# Buck_V2_1.net
KiCad netlist of a schematic drawn in EAGLE
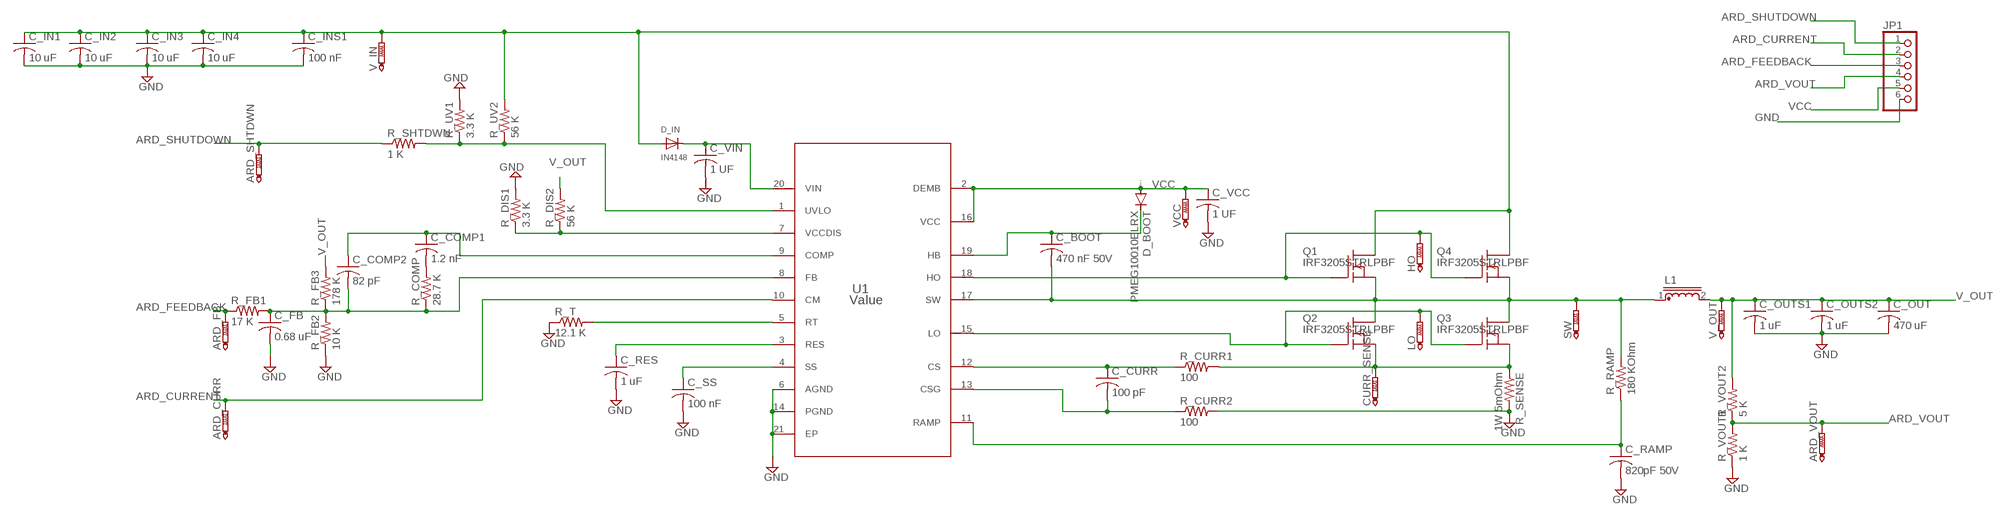
[diagram p0: schematic, sheet 1]

(export (version "E")
  (design (tool "Eeschema 10.0.6"))
  (components
    (comp (ref "ARD_CURR")
      (value "PTR1TP20R")
      (footprint "eagle-import:TP20R")
      (libsource (lib "eagle-import") (part "PTR1TP20R"))
    )
    (comp (ref "ARD_FB")
      (value "PTR1TP20R")
      (footprint "eagle-import:TP20R")
      (libsource (lib "eagle-import") (part "PTR1TP20R"))
    )
    (comp (ref "ARD_SHTDWN")
      (value "PTR1TP20R")
      (footprint "eagle-import:TP20R")
      (libsource (lib "eagle-import") (part "PTR1TP20R"))
    )
    (comp (ref "ARD_VOUT")
      (value "PTR1TP20R")
      (footprint "eagle-import:TP20R")
      (libsource (lib "eagle-import") (part "PTR1TP20R"))
    )
    (comp (ref "CURR_SENSE")
      (value "PTR1TP20R")
      (footprint "eagle-import:TP20R")
      (libsource (lib "eagle-import") (part "PTR1TP20R"))
    )
    (comp (ref "C_BOOT")
      (value "470 nF 50V")
      (footprint "eagle-import:C0603")
      (libsource (lib "eagle-import") (part "rcl_334_C-USC0603"))
    )
    (comp (ref "C_COMP1")
      (value "1.2 nF")
      (footprint "eagle-import:C0603")
      (libsource (lib "eagle-import") (part "C-USC0603"))
    )
    (comp (ref "C_COMP2")
      (value "82 pF")
      (footprint "eagle-import:C0603")
      (libsource (lib "eagle-import") (part "C-USC0603"))
    )
    (comp (ref "C_CURR")
      (value "100 pF")
      (footprint "eagle-import:C0603")
      (libsource (lib "eagle-import") (part "C-USC0603"))
    )
    (comp (ref "C_FB")
      (value "0.68 uF")
      (footprint "eagle-import:C0603")
      (libsource (lib "eagle-import") (part "C-USC0603"))
    )
    (comp (ref "C_IN1")
      (value "10 uF")
      (footprint "eagle-import:C1206")
      (libsource (lib "eagle-import") (part "C-USC1206"))
    )
    (comp (ref "C_IN2")
      (value "10 uF")
      (footprint "eagle-import:C1206")
      (libsource (lib "eagle-import") (part "C-USC1206"))
    )
    (comp (ref "C_IN3")
      (value "10 uF")
      (footprint "eagle-import:C1206")
      (libsource (lib "eagle-import") (part "C-USC1206"))
    )
    (comp (ref "C_IN4")
      (value "10 uF")
      (footprint "eagle-import:C1206")
      (fields (field (name "SPICEPREFIX") "C"))
      (libsource (lib "eagle-import") (part "C-USC1206"))
    )
    (comp (ref "C_INS1")
      (value "100 nF")
      (footprint "eagle-import:C0603")
      (libsource (lib "eagle-import") (part "C-USC0603"))
    )
    (comp (ref "C_OUT")
      (value "470 uF")
      (footprint "eagle-import:CAP_PANASONIC_H13")
      (libsource (lib "eagle-import") (part "CAP_PANASONIC_H13"))
    )
    (comp (ref "C_OUTS1")
      (value "1 uF")
      (footprint "eagle-import:C0805")
      (libsource (lib "eagle-import") (part "rcl_334_C-USC0805"))
    )
    (comp (ref "C_OUTS2")
      (value "1 uF")
      (footprint "eagle-import:C0805")
      (libsource (lib "eagle-import") (part "rcl_334_C-USC0805"))
    )
    (comp (ref "C_RAMP")
      (value "820pF 50V")
      (footprint "eagle-import:C0603")
      (libsource (lib "eagle-import") (part "rcl_334_C-USC0603"))
    )
    (comp (ref "C_RES")
      (value "1 uF")
      (footprint "eagle-import:C0603")
      (libsource (lib "eagle-import") (part "C-USC0603"))
    )
    (comp (ref "C_SS")
      (value "100 nF")
      (footprint "eagle-import:C0603")
      (libsource (lib "eagle-import") (part "C-USC0603"))
    )
    (comp (ref "C_VCC")
      (value "1 UF")
      (footprint "eagle-import:C0603")
      (libsource (lib "eagle-import") (part "rcl_334_C-USC0603"))
    )
    (comp (ref "C_VIN")
      (value "1 UF")
      (footprint "eagle-import:C0603")
      (libsource (lib "eagle-import") (part "rcl_334_C-USC0603"))
    )
    (comp (ref "D_BOOT")
      (value "PMEG10010ELRX")
      (footprint "eagle-import:SOD123")
      (libsource (lib "eagle-import") (part "DIODE-SOD123"))
    )
    (comp (ref "D_IN")
      (value "IN4148")
      (footprint "eagle-import:SOD-123")
      (libsource (lib "eagle-import") (part "DIODESOD-123"))
    )
    (comp (ref "HO")
      (value "PTR1TP20R")
      (footprint "eagle-import:TP20R")
      (libsource (lib "eagle-import") (part "PTR1TP20R"))
    )
    (comp (ref "JP1")
      (value "PINHD-1X6")
      (footprint "eagle-import:1X06")
      (libsource (lib "eagle-import") (part "PINHD-1X6"))
    )
    (comp (ref "L1")
      (value "17.5X17.5_INDUCTOR_SMD")
      (footprint "eagle-import:17.5X17.5_INDUCTOR_SMD")
      (libsource (lib "eagle-import") (part "17.5X17.5_INDUCTOR_SMD"))
    )
    (comp (ref "LO")
      (value "PTR1TP20R")
      (footprint "eagle-import:TP20R")
      (libsource (lib "eagle-import") (part "PTR1TP20R"))
    )
    (comp (ref "Q1")
      (value "IRF3205STRLPBF")
      (footprint "eagle-import:D2PAK")
      (libsource (lib "eagle-import") (part "IRF510D2PAK"))
    )
    (comp (ref "Q2")
      (value "IRF3205STRLPBF")
      (footprint "eagle-import:D2PAK")
      (libsource (lib "eagle-import") (part "IRF510D2PAK"))
    )
    (comp (ref "Q3")
      (value "IRF3205STRLPBF")
      (footprint "eagle-import:D2PAK")
      (libsource (lib "eagle-import") (part "IRF510D2PAK"))
    )
    (comp (ref "Q4")
      (value "IRF3205STRLPBF")
      (footprint "eagle-import:D2PAK")
      (libsource (lib "eagle-import") (part "IRF510D2PAK"))
    )
    (comp (ref "R_COMP")
      (value "28.7 K")
      (footprint "eagle-import:R0603")
      (libsource (lib "eagle-import") (part "R-US_R0603"))
    )
    (comp (ref "R_CURR1")
      (value "100")
      (footprint "eagle-import:R0603")
      (libsource (lib "eagle-import") (part "R-US_R0603"))
    )
    (comp (ref "R_CURR2")
      (value "100")
      (footprint "eagle-import:R0603")
      (libsource (lib "eagle-import") (part "R-US_R0603"))
    )
    (comp (ref "R_DIS1")
      (value "3.3 K")
      (footprint "eagle-import:R0603")
      (libsource (lib "eagle-import") (part "R-US_R0603"))
    )
    (comp (ref "R_DIS2")
      (value "56 K")
      (footprint "eagle-import:R0603")
      (libsource (lib "eagle-import") (part "R-US_R0603"))
    )
    (comp (ref "R_FB1")
      (value "17 K")
      (footprint "eagle-import:R0603")
      (libsource (lib "eagle-import") (part "R-US_R0603"))
    )
    (comp (ref "R_FB2")
      (value "10 K")
      (footprint "eagle-import:R0603")
      (libsource (lib "eagle-import") (part "R-US_R0603"))
    )
    (comp (ref "R_FB3")
      (value "178 K")
      (footprint "eagle-import:R0603")
      (libsource (lib "eagle-import") (part "R-US_R0603"))
    )
    (comp (ref "R_RAMP")
      (value "180 KOhm")
      (footprint "eagle-import:R0603")
      (libsource (lib "eagle-import") (part "rcl_334_R-US_R0603"))
    )
    (comp (ref "R_SENSE")
      (value "1W 5mOhm")
      (footprint "eagle-import:R2512")
      (libsource (lib "eagle-import") (part "rcl_334_R-US_R2512"))
    )
    (comp (ref "R_SHTDWN")
      (value "1 K")
      (footprint "eagle-import:R0603")
      (libsource (lib "eagle-import") (part "R-US_R0603"))
    )
    (comp (ref "R_T")
      (value "12.1 K")
      (footprint "eagle-import:R0603")
      (libsource (lib "eagle-import") (part "R-US_R0603"))
    )
    (comp (ref "R_UV1")
      (value "3.3 K")
      (footprint "eagle-import:R0603")
      (libsource (lib "eagle-import") (part "R-US_R0603"))
    )
    (comp (ref "R_UV2")
      (value "56 K")
      (footprint "eagle-import:R0603")
      (libsource (lib "eagle-import") (part "R-US_R0603"))
    )
    (comp (ref "R_VOUT1")
      (value "1 K")
      (footprint "eagle-import:R0603")
      (libsource (lib "eagle-import") (part "R-US_R0603"))
    )
    (comp (ref "R_VOUT2")
      (value "5 K")
      (footprint "eagle-import:R0603")
      (libsource (lib "eagle-import") (part "R-US_R0603"))
    )
    (comp (ref "SW")
      (value "PTR1TP20R")
      (footprint "eagle-import:TP20R")
      (libsource (lib "eagle-import") (part "PTR1TP20R"))
    )
    (comp (ref "U1")
      (value "Value")
      (footprint "eagle-import:PWP0020A")
      (fields (field (name "MANUFACTURER") "Texas Instruments") (field (name "PARTNUMBER") "LM5117PMHXNOPB"))
      (libsource (lib "eagle-import") (part "LM5117PMHX/NOPB"))
    )
    (comp (ref "VCC")
      (value "PTR1TP20R")
      (footprint "eagle-import:TP20R")
      (libsource (lib "eagle-import") (part "PTR1TP20R"))
    )
    (comp (ref "V_IN")
      (value "PTR1TP20R")
      (footprint "eagle-import:TP20R")
      (libsource (lib "eagle-import") (part "PTR1TP20R"))
    )
    (comp (ref "V_OUT")
      (value "PTR1TP20R")
      (footprint "eagle-import:TP20R")
      (libsource (lib "eagle-import") (part "PTR1TP20R"))
    )
  )
  (nets
    (net (code "1") (name "/ARD_CURRENT") (class "Default")
      (node (ref "ARD_CURR") (pin "TP") (pinfunction "TP_TP") (pintype "input"))
      (node (ref "JP1") (pin "2") (pinfunction "2_2") (pintype "passive"))
      (node (ref "U1") (pin "10") (pinfunction "CM_10") (pintype "output"))
    )
    (net (code "2") (name "/ARD_FEEDBACK") (class "Default")
      (node (ref "ARD_FB") (pin "TP") (pinfunction "TP_TP") (pintype "input"))
      (node (ref "JP1") (pin "3") (pinfunction "3_3") (pintype "passive"))
      (node (ref "R_FB1") (pin "1") (pinfunction "1_1") (pintype "passive"))
    )
    (net (code "3") (name "/ARD_SHUTDOWN") (class "Default")
      (node (ref "ARD_SHTDWN") (pin "TP") (pinfunction "TP_TP") (pintype "input"))
      (node (ref "JP1") (pin "1") (pinfunction "1_1") (pintype "passive"))
      (node (ref "R_SHTDWN") (pin "1") (pinfunction "1_1") (pintype "passive"))
    )
    (net (code "4") (name "/ARD_VOUT") (class "Default")
      (node (ref "ARD_VOUT") (pin "TP") (pinfunction "TP_TP") (pintype "input"))
      (node (ref "JP1") (pin "4") (pinfunction "4_4") (pintype "passive"))
      (node (ref "R_VOUT1") (pin "2") (pinfunction "2_2") (pintype "passive"))
      (node (ref "R_VOUT2") (pin "1") (pinfunction "1_1") (pintype "passive"))
    )
    (net (code "5") (name "/VCC") (class "Default")
      (node (ref "C_VCC") (pin "1") (pinfunction "1_1") (pintype "passive"))
      (node (ref "D_BOOT") (pin "A") (pinfunction "A_A") (pintype "passive"))
      (node (ref "JP1") (pin "5") (pinfunction "5_5") (pintype "passive"))
      (node (ref "U1") (pin "16") (pinfunction "VCC_16") (pintype "power_in"))
      (node (ref "U1") (pin "2") (pinfunction "DEMB_2") (pintype "passive"))
      (node (ref "VCC") (pin "TP") (pinfunction "TP_TP") (pintype "input"))
    )
    (net (code "6") (name "/V_OUT") (class "Default")
      (node (ref "C_OUT") (pin "P$2") (pinfunction "2_P$2") (pintype "passive"))
      (node (ref "C_OUTS1") (pin "1") (pinfunction "1_1") (pintype "passive"))
      (node (ref "C_OUTS2") (pin "1") (pinfunction "1_1") (pintype "passive"))
      (node (ref "L1") (pin "2") (pinfunction "2_2") (pintype "passive"))
      (node (ref "R_DIS2") (pin "2") (pinfunction "2_2") (pintype "passive"))
      (node (ref "R_FB3") (pin "2") (pinfunction "2_2") (pintype "passive"))
      (node (ref "R_VOUT2") (pin "2") (pinfunction "2_2") (pintype "passive"))
      (node (ref "V_OUT") (pin "TP") (pinfunction "TP_TP") (pintype "input"))
    )
    (net (code "7") (name "GND") (class "Default")
      (node (ref "C_FB") (pin "2") (pinfunction "2_2") (pintype "passive"))
      (node (ref "C_IN1") (pin "2") (pinfunction "2_2") (pintype "passive"))
      (node (ref "C_IN2") (pin "2") (pinfunction "2_2") (pintype "passive"))
      (node (ref "C_IN3") (pin "2") (pinfunction "2_2") (pintype "passive"))
      (node (ref "C_IN4") (pin "2") (pinfunction "2_2") (pintype "passive"))
      (node (ref "C_INS1") (pin "2") (pinfunction "2_2") (pintype "passive"))
      (node (ref "C_OUT") (pin "P$1") (pinfunction "1_P$1") (pintype "passive"))
      (node (ref "C_OUTS1") (pin "2") (pinfunction "2_2") (pintype "passive"))
      (node (ref "C_OUTS2") (pin "2") (pinfunction "2_2") (pintype "passive"))
      (node (ref "C_RAMP") (pin "2") (pinfunction "2_2") (pintype "passive"))
      (node (ref "C_RES") (pin "2") (pinfunction "2_2") (pintype "passive"))
      (node (ref "C_SS") (pin "2") (pinfunction "2_2") (pintype "passive"))
      (node (ref "C_VCC") (pin "2") (pinfunction "2_2") (pintype "passive"))
      (node (ref "C_VIN") (pin "2") (pinfunction "2_2") (pintype "passive"))
      (node (ref "JP1") (pin "6") (pinfunction "6_6") (pintype "passive"))
      (node (ref "R_CURR2") (pin "2") (pinfunction "2_2") (pintype "passive"))
      (node (ref "R_DIS1") (pin "2") (pinfunction "2_2") (pintype "passive"))
      (node (ref "R_FB2") (pin "1") (pinfunction "1_1") (pintype "passive"))
      (node (ref "R_SENSE") (pin "2") (pinfunction "2_2") (pintype "passive"))
      (node (ref "R_T") (pin "1") (pinfunction "1_1") (pintype "passive"))
      (node (ref "R_UV1") (pin "2") (pinfunction "2_2") (pintype "passive"))
      (node (ref "R_VOUT1") (pin "1") (pinfunction "1_1") (pintype "passive"))
      (node (ref "U1") (pin "14") (pinfunction "PGND_14") (pintype "power_in"))
      (node (ref "U1") (pin "21") (pinfunction "EP_21") (pintype "passive"))
      (node (ref "U1") (pin "6") (pinfunction "AGND_6") (pintype "power_in"))
    )
    (net (code "8") (name "Net-(C_COMP1-Pad2)") (class "Default")
      (node (ref "C_COMP1") (pin "2") (pinfunction "2_2") (pintype "passive"))
      (node (ref "R_COMP") (pin "2") (pinfunction "2_2") (pintype "passive"))
    )
    (net (code "9") (name "Net-(Q1-D)") (class "Default")
      (node (ref "C_IN1") (pin "1") (pinfunction "1_1") (pintype "passive"))
      (node (ref "C_IN2") (pin "1") (pinfunction "1_1") (pintype "passive"))
      (node (ref "C_IN3") (pin "1") (pinfunction "1_1") (pintype "passive"))
      (node (ref "C_IN4") (pin "1") (pinfunction "1_1") (pintype "passive"))
      (node (ref "C_INS1") (pin "1") (pinfunction "1_1") (pintype "passive"))
      (node (ref "D_IN") (pin "A") (pinfunction "A_A") (pintype "passive"))
      (node (ref "Q1") (pin "2") (pinfunction "D_2") (pintype "passive"))
      (node (ref "Q4") (pin "2") (pinfunction "D_2") (pintype "passive"))
      (node (ref "R_UV2") (pin "2") (pinfunction "2_2") (pintype "passive"))
      (node (ref "V_IN") (pin "TP") (pinfunction "TP_TP") (pintype "input"))
    )
    (net (code "10") (name "Net-(Q1-G)") (class "Default")
      (node (ref "HO") (pin "TP") (pinfunction "TP_TP") (pintype "input"))
      (node (ref "Q1") (pin "1") (pinfunction "G_1") (pintype "passive"))
      (node (ref "Q4") (pin "1") (pinfunction "G_1") (pintype "passive"))
      (node (ref "U1") (pin "18") (pinfunction "HO_18") (pintype "output"))
    )
    (net (code "11") (name "Net-(Q1-S)") (class "Default")
      (node (ref "C_BOOT") (pin "2") (pinfunction "2_2") (pintype "passive"))
      (node (ref "L1") (pin "1") (pinfunction "1_1") (pintype "passive"))
      (node (ref "Q1") (pin "3") (pinfunction "S_3") (pintype "passive"))
      (node (ref "Q2") (pin "2") (pinfunction "D_2") (pintype "passive"))
      (node (ref "Q3") (pin "2") (pinfunction "D_2") (pintype "passive"))
      (node (ref "Q4") (pin "3") (pinfunction "S_3") (pintype "passive"))
      (node (ref "R_RAMP") (pin "2") (pinfunction "2_2") (pintype "passive"))
      (node (ref "SW") (pin "TP") (pinfunction "TP_TP") (pintype "input"))
      (node (ref "U1") (pin "17") (pinfunction "SW_17") (pintype "power_in"))
    )
    (net (code "12") (name "Net-(Q2-G)") (class "Default")
      (node (ref "LO") (pin "TP") (pinfunction "TP_TP") (pintype "input"))
      (node (ref "Q2") (pin "1") (pinfunction "G_1") (pintype "passive"))
      (node (ref "Q3") (pin "1") (pinfunction "G_1") (pintype "passive"))
      (node (ref "U1") (pin "15") (pinfunction "LO_15") (pintype "output"))
    )
    (net (code "13") (name "Net-(Q2-S)") (class "Default")
      (node (ref "CURR_SENSE") (pin "TP") (pinfunction "TP_TP") (pintype "input"))
      (node (ref "Q2") (pin "3") (pinfunction "S_3") (pintype "passive"))
      (node (ref "Q3") (pin "3") (pinfunction "S_3") (pintype "passive"))
      (node (ref "R_CURR1") (pin "2") (pinfunction "2_2") (pintype "passive"))
      (node (ref "R_SENSE") (pin "1") (pinfunction "1_1") (pintype "passive"))
    )
    (net (code "14") (name "Net-(U1-COMP)") (class "Default")
      (node (ref "C_COMP1") (pin "1") (pinfunction "1_1") (pintype "passive"))
      (node (ref "C_COMP2") (pin "1") (pinfunction "1_1") (pintype "passive"))
      (node (ref "U1") (pin "9") (pinfunction "COMP_9") (pintype "output"))
    )
    (net (code "15") (name "Net-(U1-CS)") (class "Default")
      (node (ref "C_CURR") (pin "1") (pinfunction "1_1") (pintype "passive"))
      (node (ref "R_CURR1") (pin "1") (pinfunction "1_1") (pintype "passive"))
      (node (ref "U1") (pin "12") (pinfunction "CS_12") (pintype "input"))
    )
    (net (code "16") (name "Net-(U1-CSG)") (class "Default")
      (node (ref "C_CURR") (pin "2") (pinfunction "2_2") (pintype "passive"))
      (node (ref "R_CURR2") (pin "1") (pinfunction "1_1") (pintype "passive"))
      (node (ref "U1") (pin "13") (pinfunction "CSG_13") (pintype "input"))
    )
    (net (code "17") (name "Net-(U1-FB)") (class "Default")
      (node (ref "C_COMP2") (pin "2") (pinfunction "2_2") (pintype "passive"))
      (node (ref "C_FB") (pin "1") (pinfunction "1_1") (pintype "passive"))
      (node (ref "R_COMP") (pin "1") (pinfunction "1_1") (pintype "passive"))
      (node (ref "R_FB1") (pin "2") (pinfunction "2_2") (pintype "passive"))
      (node (ref "R_FB2") (pin "2") (pinfunction "2_2") (pintype "passive"))
      (node (ref "R_FB3") (pin "1") (pinfunction "1_1") (pintype "passive"))
      (node (ref "U1") (pin "8") (pinfunction "FB_8") (pintype "input"))
    )
    (net (code "18") (name "Net-(U1-HB)") (class "Default")
      (node (ref "C_BOOT") (pin "1") (pinfunction "1_1") (pintype "passive"))
      (node (ref "D_BOOT") (pin "C") (pinfunction "C_C") (pintype "passive"))
      (node (ref "U1") (pin "19") (pinfunction "HB_19") (pintype "output"))
    )
    (net (code "19") (name "Net-(U1-RAMP)") (class "Default")
      (node (ref "C_RAMP") (pin "1") (pinfunction "1_1") (pintype "passive"))
      (node (ref "R_RAMP") (pin "1") (pinfunction "1_1") (pintype "passive"))
      (node (ref "U1") (pin "11") (pinfunction "RAMP_11") (pintype "input"))
    )
    (net (code "20") (name "Net-(U1-RES)") (class "Default")
      (node (ref "C_RES") (pin "1") (pinfunction "1_1") (pintype "passive"))
      (node (ref "U1") (pin "3") (pinfunction "RES_3") (pintype "input"))
    )
    (net (code "21") (name "Net-(U1-RT)") (class "Default")
      (node (ref "R_T") (pin "2") (pinfunction "2_2") (pintype "passive"))
      (node (ref "U1") (pin "5") (pinfunction "RT_5") (pintype "input"))
    )
    (net (code "22") (name "Net-(U1-SS)") (class "Default")
      (node (ref "C_SS") (pin "1") (pinfunction "1_1") (pintype "passive"))
      (node (ref "U1") (pin "4") (pinfunction "SS_4") (pintype "input"))
    )
    (net (code "23") (name "Net-(U1-UVLO)") (class "Default")
      (node (ref "R_SHTDWN") (pin "2") (pinfunction "2_2") (pintype "passive"))
      (node (ref "R_UV1") (pin "1") (pinfunction "1_1") (pintype "passive"))
      (node (ref "R_UV2") (pin "1") (pinfunction "1_1") (pintype "passive"))
      (node (ref "U1") (pin "1") (pinfunction "UVLO_1") (pintype "input"))
    )
    (net (code "24") (name "Net-(U1-VCCDIS)") (class "Default")
      (node (ref "R_DIS1") (pin "1") (pinfunction "1_1") (pintype "passive"))
      (node (ref "R_DIS2") (pin "1") (pinfunction "1_1") (pintype "passive"))
      (node (ref "U1") (pin "7") (pinfunction "VCCDIS_7") (pintype "passive"))
    )
    (net (code "25") (name "Net-(U1-VIN)") (class "Default")
      (node (ref "C_VIN") (pin "1") (pinfunction "1_1") (pintype "passive"))
      (node (ref "D_IN") (pin "C") (pinfunction "C_C") (pintype "passive"))
      (node (ref "U1") (pin "20") (pinfunction "VIN_20") (pintype "power_in"))
    )
  )
)
